# DC-DC.net
KiCad netlist of a schematic drawn in Altium Designer
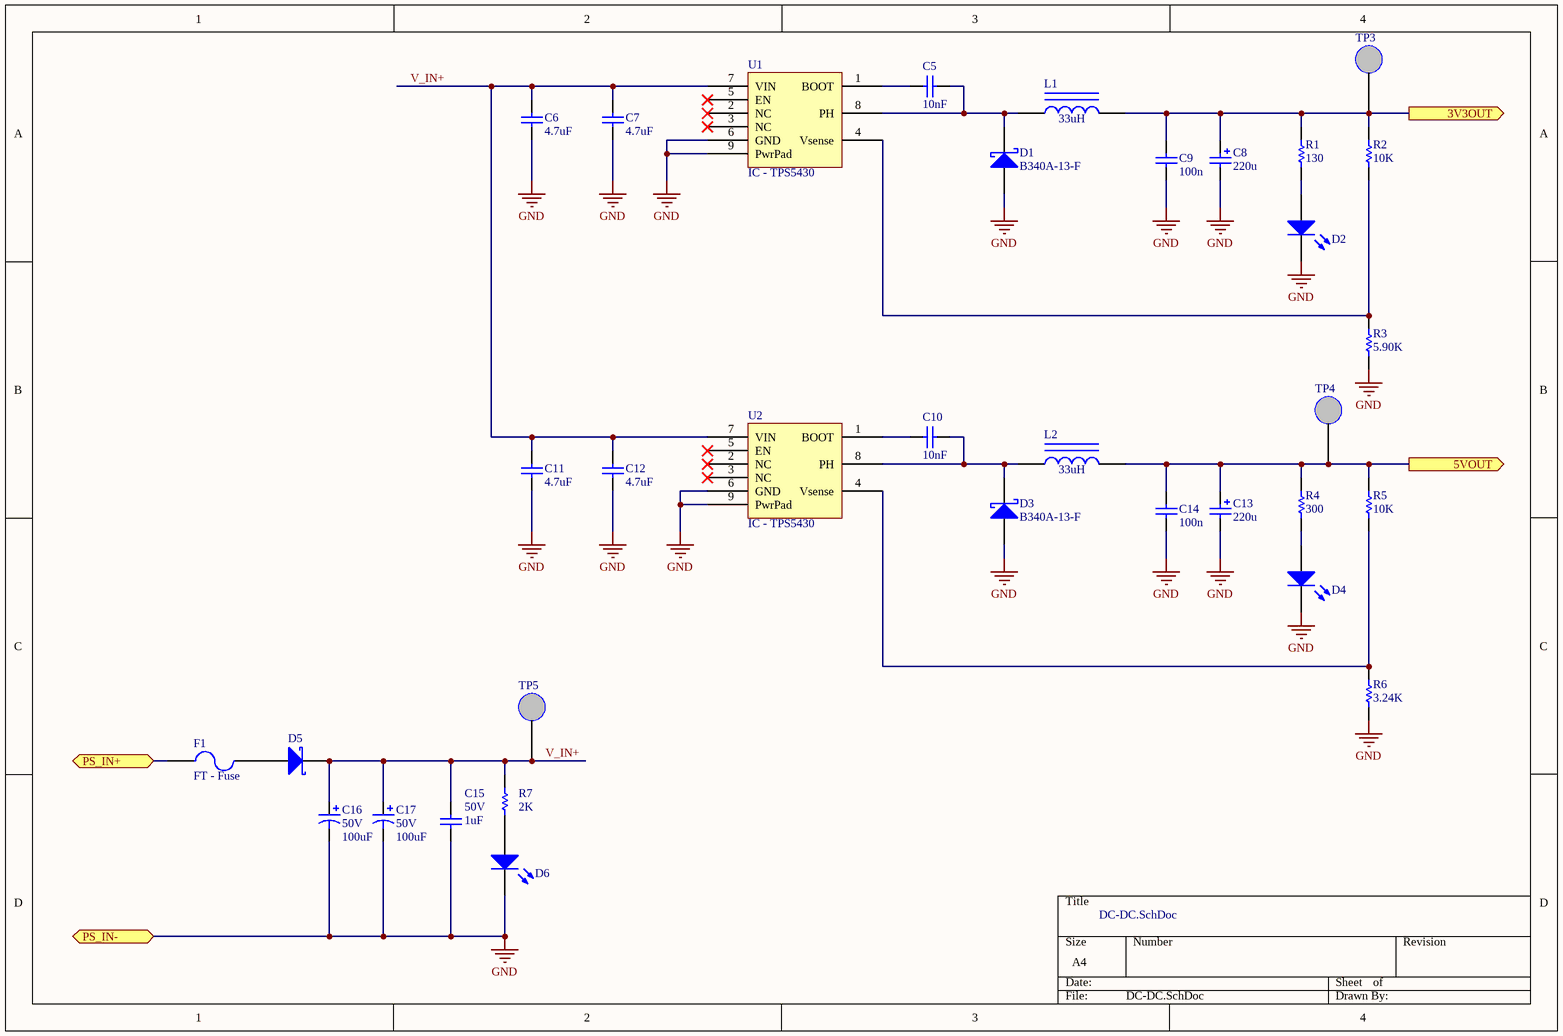
[diagram p0: DC-DC.SchDoc]

(export (version "E")
  (design (tool "Eeschema 10.0.6"))
  (components
    (comp (ref "C5")
      (value "10nF")
      (footprint "CS-0603")
      (description "CAP CER 10000PF 50V 10% X7R 0603")
      (fields (field (name "TOLERANCE") "10%") (field (name "MANUFACTURER") "TDK"))
      (libsource (lib "CHINOOK_LIBRARY") (part "CS - CAPACITOR"))
    )
    (comp (ref "C6")
      (value "4.7uF")
      (footprint "CS-1206")
      (fields
        (field (name "TOLERANCE") "10%")
        (field (name "MANUFACTURER") "Samsung")
        (field (name "VOLTAGE") "16V")
      )
      (libsource (lib "CHINOOK_LIBRARY") (part "CS - CAPACITOR"))
    )
    (comp (ref "C7")
      (value "4.7uF")
      (footprint "CS-1206")
      (fields
        (field (name "TOLERANCE") "10%")
        (field (name "MANUFACTURER") "Samsung")
        (field (name "VOLTAGE") "16V")
      )
      (libsource (lib "CHINOOK_LIBRARY") (part "CS - CAPACITOR"))
    )
    (comp (ref "C8")
      (value "220u")
      (footprint "CS-2312")
      (fields
        (field (name "TOLERANCE") "10%")
        (field (name "VOLTAGE") "VOLTAGE")
        (field (name "Comment") "CS - CAPACITOR POL")
      )
      (libsource (lib "CHINOOK-FOOTPRINT") (part "CS - CAPACITOR POL"))
    )
    (comp (ref "C9")
      (value "100n")
      (footprint "CS-0603")
      (fields
        (field (name "TOLERANCE") "10%")
        (field (name "VOLTAGE") "16V")
        (field (name "Comment") "CS - CAPACITOR")
      )
      (libsource (lib "CHINOOK_LIBRARY") (part "CS - CAPACITOR"))
    )
    (comp (ref "C10")
      (value "10nF")
      (footprint "CS-0603")
      (description "CAP CER 10000PF 50V 10% X7R 0603")
      (fields (field (name "TOLERANCE") "10%") (field (name "MANUFACTURER") "TDK"))
      (libsource (lib "CHINOOK_LIBRARY") (part "CS - CAPACITOR"))
    )
    (comp (ref "C11")
      (value "4.7uF")
      (footprint "CS-1206")
      (fields
        (field (name "TOLERANCE") "10%")
        (field (name "MANUFACTURER") "Samsung")
        (field (name "VOLTAGE") "16V")
      )
      (libsource (lib "CHINOOK_LIBRARY") (part "CS - CAPACITOR"))
    )
    (comp (ref "C12")
      (value "4.7uF")
      (footprint "CS-1206")
      (fields
        (field (name "TOLERANCE") "10%")
        (field (name "MANUFACTURER") "Samsung")
        (field (name "VOLTAGE") "16V")
      )
      (libsource (lib "CHINOOK_LIBRARY") (part "CS - CAPACITOR"))
    )
    (comp (ref "C13")
      (value "220u")
      (footprint "CS-2312")
      (fields
        (field (name "TOLERANCE") "10%")
        (field (name "VOLTAGE") "VOLTAGE")
        (field (name "Comment") "CS - CAPACITOR POL")
      )
      (libsource (lib "CHINOOK-FOOTPRINT") (part "CS - CAPACITOR POL"))
    )
    (comp (ref "C14")
      (value "100n")
      (footprint "CS-0603")
      (fields
        (field (name "TOLERANCE") "10%")
        (field (name "VOLTAGE") "16V")
        (field (name "Comment") "CS - CAPACITOR")
      )
      (libsource (lib "CHINOOK_LIBRARY") (part "CS - CAPACITOR"))
    )
    (comp (ref "C15")
      (value "1uF")
      (footprint "CS-0603")
      (fields
        (field (name "TOLERANCE") "10%")
        (field (name "VOLTAGE") "50V")
        (field (name "Comment") "CS - CAPACITOR")
      )
      (libsource (lib "CHINOOK_LIBRARY") (part "CS - CAPACITOR"))
    )
    (comp (ref "C16")
      (value "100uF")
      (footprint "CT-CAP-ALUM-8X14")
      (fields
        (field (name "TOLERANCE") "10%")
        (field (name "VOLTAGE") "50V")
        (field (name "Comment") "CT - CAPACITOR ELECTROLYTIC")
      )
      (libsource (lib "CHINOOK_LIBRARY") (part "CT - CAPACITOR ELECTROLYTIC"))
    )
    (comp (ref "C17")
      (value "100uF")
      (footprint "CT-CAP-ALUM-8X14")
      (fields
        (field (name "TOLERANCE") "10%")
        (field (name "VOLTAGE") "50V")
        (field (name "Comment") "CT - CAPACITOR ELECTROLYTIC")
      )
      (libsource (lib "CHINOOK_LIBRARY") (part "CT - CAPACITOR ELECTROLYTIC"))
    )
    (comp (ref "D1")
      (value "B340A-13-F")
      (footprint "DS-DO-214AC-SMA")
      (description "DIODE SCHOTTKY 40V 3A SMA")
      (fields (field (name "MANUFACTURER") "Diodes Incorporated"))
      (libsource (lib "CHINOOK_LIBRARY") (part "DS - Schottky"))
    )
    (comp (ref "D2")
      (value "LED - NORMAL LED")
      (footprint "LED-0603 YELLOW")
      (libsource (lib "CHINOOK_LIBRARY") (part "LED - NORMAL LED"))
    )
    (comp (ref "D3")
      (value "B340A-13-F")
      (footprint "DS-DO-214AC-SMA")
      (description "DIODE SCHOTTKY 40V 3A SMA")
      (fields (field (name "MANUFACTURER") "Diodes Incorporated"))
      (libsource (lib "CHINOOK_LIBRARY") (part "DS - Schottky"))
    )
    (comp (ref "D4")
      (value "LED - NORMAL LED")
      (footprint "LED-0603 YELLOW")
      (libsource (lib "CHINOOK_LIBRARY") (part "LED - NORMAL LED"))
    )
    (comp (ref "D5")
      (value "DT - Diode")
      (footprint "TO-220AC")
      (description "Zener Schottky")
      (libsource (lib "Miscellaneous Devices") (part "Diode 18TQ045"))
    )
    (comp (ref "D6")
      (value "LED - NORMAL LED")
      (footprint "LED-0603 YELLOW")
      (libsource (lib "CHINOOK_LIBRARY") (part "LED - NORMAL LED"))
    )
    (comp (ref "F1")
      (value "FT - Fuse")
      (footprint "FT - 5mm x 20mm")
      (fields (field (name "MANUFACTURER") "Schurter Inc"))
      (libsource (lib "CHINOOK_LIBRARY") (part "FT - Fuse"))
    )
    (comp (ref "L1")
      (value "33uH")
      (footprint "LS-Inductor SMD")
      (description "INDUCTOR SHIELD PWR")
      (fields (field (name "MANUFACTURER") "Bourns Inc") (field (name "Comment") "LS - INDUCTOR"))
      (libsource (lib "CHINOOK_LIBRARY") (part "LS - INDUCTOR"))
    )
    (comp (ref "L2")
      (value "33uH")
      (footprint "LS-Inductor SMD")
      (description "INDUCTOR SHIELD PWR")
      (fields (field (name "MANUFACTURER") "Bourns Inc") (field (name "Comment") "LS - INDUCTOR"))
      (libsource (lib "CHINOOK_LIBRARY") (part "LS - INDUCTOR"))
    )
    (comp (ref "R1")
      (value "130")
      (footprint "RS-0603")
      (fields
        (field (name "TOLERANCE") "RES TOL")
        (field (name "POWER") "RES POWER")
        (field (name "Comment") "RS - RESISTOR")
      )
      (libsource (lib "CHINOOK_LIBRARY") (part "RS - RESISTOR"))
    )
    (comp (ref "R2")
      (value "10K")
      (footprint "RS-0603")
      (fields
        (field (name "TOLERANCE") "RES TOL")
        (field (name "POWER") "RES POWER")
        (field (name "Comment") "RS - RESISTOR")
      )
      (libsource (lib "CHINOOK_LIBRARY") (part "RS - RESISTOR"))
    )
    (comp (ref "R3")
      (value "5.90K")
      (footprint "RS-0603")
      (fields
        (field (name "TOLERANCE") "RES TOL")
        (field (name "POWER") "RES POWER")
        (field (name "Comment") "RS - RESISTOR")
      )
      (libsource (lib "CHINOOK_LIBRARY") (part "RS - RESISTOR"))
    )
    (comp (ref "R4")
      (value "300")
      (footprint "RS-0603")
      (fields
        (field (name "TOLERANCE") "RES TOL")
        (field (name "POWER") "RES POWER")
        (field (name "Comment") "RS - RESISTOR")
      )
      (libsource (lib "CHINOOK_LIBRARY") (part "RS - RESISTOR"))
    )
    (comp (ref "R5")
      (value "10K")
      (footprint "RS-0603")
      (fields
        (field (name "TOLERANCE") "RES TOL")
        (field (name "POWER") "RES POWER")
        (field (name "Comment") "RS - RESISTOR")
      )
      (libsource (lib "CHINOOK_LIBRARY") (part "RS - RESISTOR"))
    )
    (comp (ref "R6")
      (value "3.24K")
      (footprint "RS-0603")
      (fields
        (field (name "TOLERANCE") "RES TOL")
        (field (name "POWER") "RES POWER")
        (field (name "Comment") "RS - RESISTOR")
      )
      (libsource (lib "CHINOOK_LIBRARY") (part "RS - RESISTOR"))
    )
    (comp (ref "R7")
      (value "2K")
      (footprint "RS-0603")
      (fields
        (field (name "TOLERANCE") "RES TOL")
        (field (name "POWER") "1/10W")
        (field (name "Comment") "RS - RESISTOR")
      )
      (libsource (lib "CHINOOK_LIBRARY") (part "RS - RESISTOR"))
    )
    (comp (ref "TP3")
      (value "5003K")
      (footprint "TP - VERTICAL")
      (libsource (lib "CHINOOK_LIBRARY") (part "TP - Test point vertical"))
    )
    (comp (ref "TP4")
      (value "5003K")
      (footprint "TP - VERTICAL")
      (libsource (lib "CHINOOK_LIBRARY") (part "TP - Test point vertical"))
    )
    (comp (ref "TP5")
      (value "5003K")
      (footprint "TP - VERTICAL")
      (libsource (lib "CHINOOK_LIBRARY") (part "TP - Test point vertical"))
    )
    (comp (ref "U1")
      (value "IC - TPS5430")
      (footprint "IC-SOIC8-POWERPAD")
      (description "IC REG BUCK ADJ 3A 8SOPWRPAD")
      (fields (field (name "MANUFACTURER") "Texas Instruments") (field (name "PART NUMBER") "TPS5430"))
      (libsource (lib "CHINOOK_LIBRARY") (part "IC - TPS5430"))
    )
    (comp (ref "U2")
      (value "IC - TPS5430")
      (footprint "IC-SOIC8-POWERPAD")
      (description "IC REG BUCK ADJ 3A 8SOPWRPAD")
      (fields (field (name "MANUFACTURER") "Texas Instruments") (field (name "PART NUMBER") "TPS5430"))
      (libsource (lib "CHINOOK_LIBRARY") (part "IC - TPS5430"))
    )
  )
  (nets
    (net (code "1") (name "/3V3OUT") (class "Default")
      (node (ref "C8") (pin "1") (pinfunction "1_1") (pintype "passive"))
      (node (ref "C9") (pin "2") (pinfunction "2_2") (pintype "passive"))
      (node (ref "L1") (pin "2") (pinfunction "2_2") (pintype "passive"))
      (node (ref "R1") (pin "1") (pinfunction "1_1") (pintype "passive"))
      (node (ref "R2") (pin "1") (pinfunction "1_1") (pintype "passive"))
      (node (ref "TP3") (pin "1") (pinfunction "1_1") (pintype "passive"))
    )
    (net (code "2") (name "/5VOUT") (class "Default")
      (node (ref "C13") (pin "1") (pinfunction "1_1") (pintype "passive"))
      (node (ref "C14") (pin "2") (pinfunction "2_2") (pintype "passive"))
      (node (ref "L2") (pin "2") (pinfunction "2_2") (pintype "passive"))
      (node (ref "R4") (pin "1") (pinfunction "1_1") (pintype "passive"))
      (node (ref "R5") (pin "1") (pinfunction "1_1") (pintype "passive"))
      (node (ref "TP4") (pin "1") (pinfunction "1_1") (pintype "passive"))
    )
    (net (code "3") (name "/PS_IN+") (class "Default")
      (node (ref "F1") (pin "1") (pinfunction "1_1") (pintype "passive"))
    )
    (net (code "4") (name "/V_IN+") (class "Default")
      (node (ref "C11") (pin "2") (pinfunction "2_2") (pintype "passive"))
      (node (ref "C12") (pin "2") (pinfunction "2_2") (pintype "passive"))
      (node (ref "C15") (pin "2") (pinfunction "2_2") (pintype "passive"))
      (node (ref "C16") (pin "1") (pinfunction "1_1") (pintype "passive"))
      (node (ref "C17") (pin "1") (pinfunction "1_1") (pintype "passive"))
      (node (ref "C6") (pin "2") (pinfunction "2_2") (pintype "passive"))
      (node (ref "C7") (pin "2") (pinfunction "2_2") (pintype "passive"))
      (node (ref "D5") (pin "1") (pinfunction "K_1") (pintype "passive"))
      (node (ref "R7") (pin "2") (pinfunction "2_2") (pintype "passive"))
      (node (ref "TP5") (pin "1") (pinfunction "1_1") (pintype "passive"))
      (node (ref "U1") (pin "7") (pinfunction "VIN_7") (pintype "passive"))
      (node (ref "U2") (pin "7") (pinfunction "VIN_7") (pintype "passive"))
    )
    (net (code "5") (name "GND") (class "Default")
      (node (ref "C11") (pin "1") (pinfunction "1_1") (pintype "passive"))
      (node (ref "C12") (pin "1") (pinfunction "1_1") (pintype "passive"))
      (node (ref "C13") (pin "2") (pinfunction "2_2") (pintype "passive"))
      (node (ref "C14") (pin "1") (pinfunction "1_1") (pintype "passive"))
      (node (ref "C15") (pin "1") (pinfunction "1_1") (pintype "passive"))
      (node (ref "C16") (pin "2") (pinfunction "2_2") (pintype "passive"))
      (node (ref "C17") (pin "2") (pinfunction "2_2") (pintype "passive"))
      (node (ref "C6") (pin "1") (pinfunction "1_1") (pintype "passive"))
      (node (ref "C7") (pin "1") (pinfunction "1_1") (pintype "passive"))
      (node (ref "C8") (pin "2") (pinfunction "2_2") (pintype "passive"))
      (node (ref "C9") (pin "1") (pinfunction "1_1") (pintype "passive"))
      (node (ref "D1") (pin "A") (pinfunction "A_A") (pintype "passive"))
      (node (ref "D2") (pin "K") (pinfunction "K_K") (pintype "passive"))
      (node (ref "D3") (pin "A") (pinfunction "A_A") (pintype "passive"))
      (node (ref "D4") (pin "K") (pinfunction "K_K") (pintype "passive"))
      (node (ref "D6") (pin "K") (pinfunction "K_K") (pintype "passive"))
      (node (ref "R3") (pin "2") (pinfunction "2_2") (pintype "passive"))
      (node (ref "R6") (pin "2") (pinfunction "2_2") (pintype "passive"))
      (node (ref "U1") (pin "6") (pinfunction "GND_6") (pintype "passive"))
      (node (ref "U1") (pin "9") (pinfunction "PwrPad_9") (pintype "passive"))
      (node (ref "U2") (pin "6") (pinfunction "GND_6") (pintype "passive"))
      (node (ref "U2") (pin "9") (pinfunction "PwrPad_9") (pintype "passive"))
    )
    (net (code "6") (name "Net-(D2-PadA)") (class "Default")
      (node (ref "D2") (pin "A") (pinfunction "A_A") (pintype "passive"))
      (node (ref "R1") (pin "2") (pinfunction "2_2") (pintype "passive"))
    )
    (net (code "7") (name "Net-(D4-PadA)") (class "Default")
      (node (ref "D4") (pin "A") (pinfunction "A_A") (pintype "passive"))
      (node (ref "R4") (pin "2") (pinfunction "2_2") (pintype "passive"))
    )
    (net (code "8") (name "Net-(D5-A)") (class "Default")
      (node (ref "D5") (pin "3") (pinfunction "A_3") (pintype "passive"))
      (node (ref "F1") (pin "2") (pinfunction "2_2") (pintype "passive"))
    )
    (net (code "9") (name "Net-(D6-PadA)") (class "Default")
      (node (ref "D6") (pin "A") (pinfunction "A_A") (pintype "passive"))
      (node (ref "R7") (pin "1") (pinfunction "1_1") (pintype "passive"))
    )
    (net (code "10") (name "Net-(U1-BOOT)") (class "Default")
      (node (ref "C5") (pin "2") (pinfunction "2_2") (pintype "passive"))
      (node (ref "U1") (pin "1") (pinfunction "BOOT_1") (pintype "passive"))
    )
    (net (code "11") (name "Net-(U1-PH)") (class "Default")
      (node (ref "C5") (pin "1") (pinfunction "1_1") (pintype "passive"))
      (node (ref "D1") (pin "K") (pinfunction "K_K") (pintype "passive"))
      (node (ref "L1") (pin "1") (pinfunction "1_1") (pintype "passive"))
      (node (ref "U1") (pin "8") (pinfunction "PH_8") (pintype "passive"))
    )
    (net (code "12") (name "Net-(U1-Vsense)") (class "Default")
      (node (ref "R2") (pin "2") (pinfunction "2_2") (pintype "passive"))
      (node (ref "R3") (pin "1") (pinfunction "1_1") (pintype "passive"))
      (node (ref "U1") (pin "4") (pinfunction "Vsense_4") (pintype "passive"))
    )
    (net (code "13") (name "Net-(U2-BOOT)") (class "Default")
      (node (ref "C10") (pin "2") (pinfunction "2_2") (pintype "passive"))
      (node (ref "U2") (pin "1") (pinfunction "BOOT_1") (pintype "passive"))
    )
    (net (code "14") (name "Net-(U2-PH)") (class "Default")
      (node (ref "C10") (pin "1") (pinfunction "1_1") (pintype "passive"))
      (node (ref "D3") (pin "K") (pinfunction "K_K") (pintype "passive"))
      (node (ref "L2") (pin "1") (pinfunction "1_1") (pintype "passive"))
      (node (ref "U2") (pin "8") (pinfunction "PH_8") (pintype "passive"))
    )
    (net (code "15") (name "Net-(U2-Vsense)") (class "Default")
      (node (ref "R5") (pin "2") (pinfunction "2_2") (pintype "passive"))
      (node (ref "R6") (pin "1") (pinfunction "1_1") (pintype "passive"))
      (node (ref "U2") (pin "4") (pinfunction "Vsense_4") (pintype "passive"))
    )
    (net (code "16") (name "unconnected-(U1-EN-Pad5)") (class "Default")
      (node (ref "U1") (pin "5") (pinfunction "EN_5") (pintype "passive+no_connect"))
    )
    (net (code "17") (name "unconnected-(U1-NC-Pad2)") (class "Default")
      (node (ref "U1") (pin "2") (pinfunction "NC_2") (pintype "passive+no_connect"))
    )
    (net (code "18") (name "unconnected-(U1-NC-Pad3)") (class "Default")
      (node (ref "U1") (pin "3") (pinfunction "NC_3") (pintype "passive+no_connect"))
    )
    (net (code "19") (name "unconnected-(U2-EN-Pad5)") (class "Default")
      (node (ref "U2") (pin "5") (pinfunction "EN_5") (pintype "passive+no_connect"))
    )
    (net (code "20") (name "unconnected-(U2-NC-Pad2)") (class "Default")
      (node (ref "U2") (pin "2") (pinfunction "NC_2") (pintype "passive+no_connect"))
    )
    (net (code "21") (name "unconnected-(U2-NC-Pad3)") (class "Default")
      (node (ref "U2") (pin "3") (pinfunction "NC_3") (pintype "passive+no_connect"))
    )
  )
)
